# MB1-MCU-r1_0.net
KiCad netlist of a schematic drawn in Altium Designer
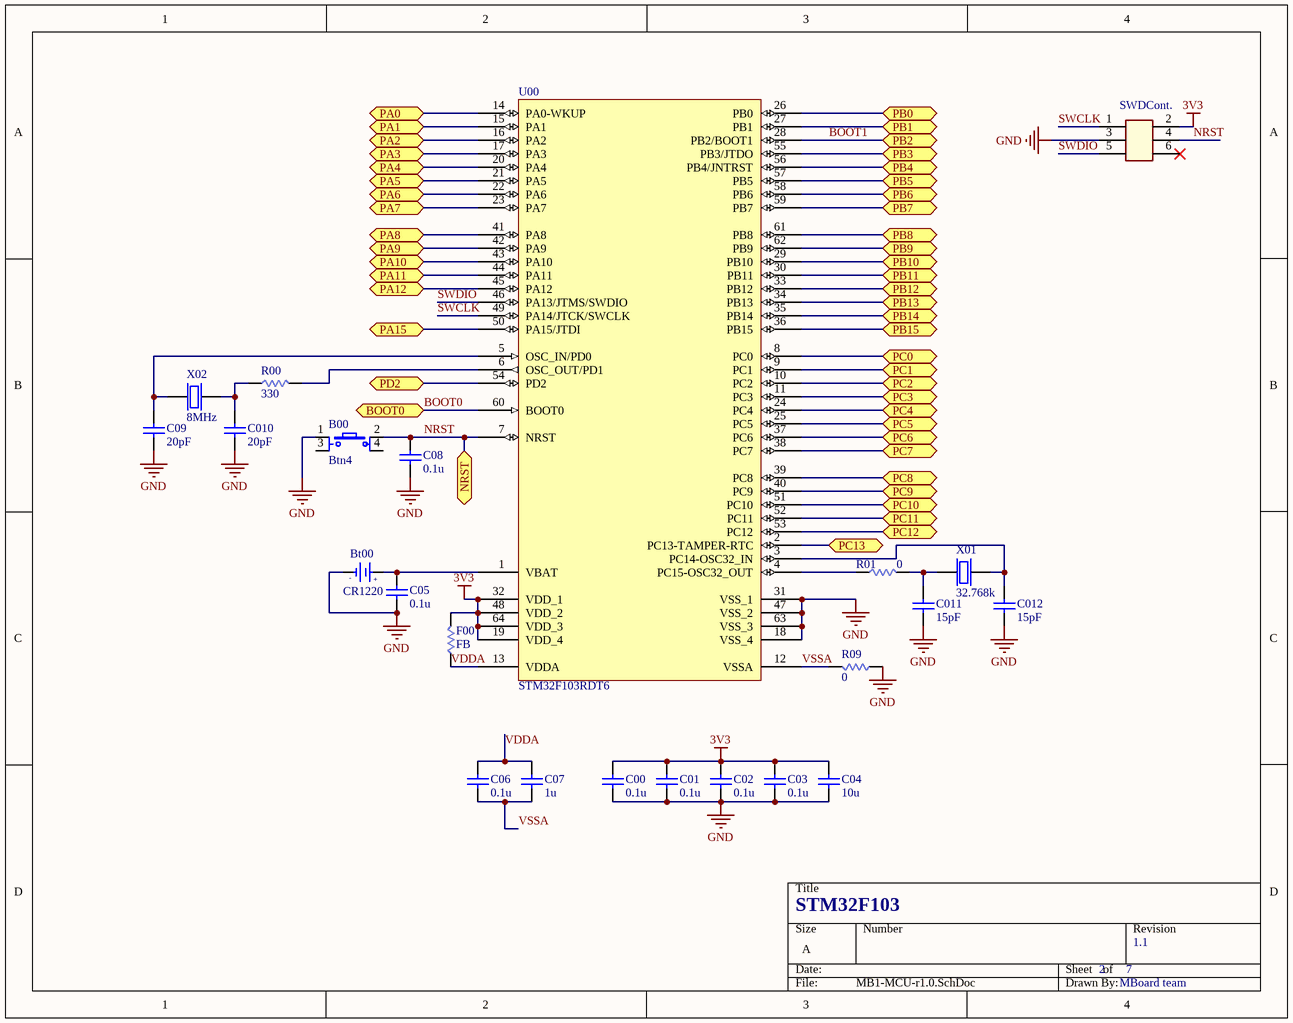
[diagram p0: MB1-MCU-r1.0.SchDoc]

(export (version "E")
  (design (tool "Eeschema 10.0.6"))
  (components
    (comp (ref "B00")
      (value "Btn4")
      (footprint "Horizon_SW_4pin_rectangular")
      (libsource (lib "MyLib") (part "Btn4"))
    )
    (comp (ref "Bt00")
      (value "CR1220")
      (footprint "MyLib:PIN3VSOCKET-SMD")
      (description "Battery 3VDC")
      (fields (field (name "Comment") "PIN 3V"))
      (libsource (lib "VioletofSun") (part "PIN 3V"))
    )
    (comp (ref "C00")
      (value "0.1u")
      (footprint "SM_0805_LD")
      (description "Non-polarity ceramic capacitor")
      (fields (field (name "Comment") "CAP Ceramic") (field (name "PUBLISHER") "Altium Limited"))
      (libsource (lib "HLib_schematic_lib") (part "CAP Ceramic"))
    )
    (comp (ref "C01")
      (value "0.1u")
      (footprint "SM_0805_LD")
      (description "Non-polarity ceramic capacitor")
      (fields (field (name "Comment") "CAP Ceramic") (field (name "PUBLISHER") "Altium Limited"))
      (libsource (lib "HLib_schematic_lib") (part "CAP Ceramic"))
    )
    (comp (ref "C02")
      (value "0.1u")
      (footprint "SM_0805_LD")
      (description "Non-polarity ceramic capacitor")
      (fields (field (name "Comment") "CAP Ceramic") (field (name "PUBLISHER") "Altium Limited"))
      (libsource (lib "HLib_schematic_lib") (part "CAP Ceramic"))
    )
    (comp (ref "C03")
      (value "0.1u")
      (footprint "SM_0805_LD")
      (description "Non-polarity ceramic capacitor")
      (fields (field (name "Comment") "CAP Ceramic") (field (name "PUBLISHER") "Altium Limited"))
      (libsource (lib "HLib_schematic_lib") (part "CAP Ceramic"))
    )
    (comp (ref "C04")
      (value "10u")
      (footprint "SM_0805_LD")
      (description "Non-polarity ceramic capacitor")
      (fields (field (name "Comment") "CAP Ceramic") (field (name "PUBLISHER") "Altium Limited"))
      (libsource (lib "HLib_schematic_lib") (part "CAP Ceramic"))
    )
    (comp (ref "C05")
      (value "0.1u")
      (footprint "SM_0805_LD")
      (description "Non-polarity ceramic capacitor")
      (fields (field (name "Comment") "CAP Ceramic") (field (name "PUBLISHER") "Altium Limited"))
      (libsource (lib "HLib_schematic_lib") (part "CAP Ceramic"))
    )
    (comp (ref "C06")
      (value "0.1u")
      (footprint "SM_0805_LD")
      (description "Non-polarity ceramic capacitor")
      (fields (field (name "Comment") "CAP Ceramic") (field (name "PUBLISHER") "Altium Limited"))
      (libsource (lib "HLib_schematic_lib") (part "CAP Ceramic"))
    )
    (comp (ref "C07")
      (value "1u")
      (footprint "SM_0805_LD")
      (description "Non-polarity ceramic capacitor")
      (fields (field (name "Comment") "CAP Ceramic") (field (name "PUBLISHER") "Altium Limited"))
      (libsource (lib "HLib_schematic_lib") (part "CAP Ceramic"))
    )
    (comp (ref "C08")
      (value "0.1u")
      (footprint "SM_0805_LD")
      (description "Non-polarity ceramic capacitor")
      (fields (field (name "Comment") "CAP Ceramic") (field (name "PUBLISHER") "Altium Limited"))
      (libsource (lib "HLib_schematic_lib") (part "CAP Ceramic"))
    )
    (comp (ref "C09")
      (value "20pF")
      (footprint "SM_0805_LD")
      (description "Non-polarity ceramic capacitor")
      (fields (field (name "Comment") "CAP Ceramic") (field (name "PUBLISHER") "Altium Limited"))
      (libsource (lib "HLib_schematic_lib") (part "CAP Ceramic"))
    )
    (comp (ref "C010")
      (value "20pF")
      (footprint "SM_0805_LD")
      (description "Non-polarity ceramic capacitor")
      (fields (field (name "Comment") "CAP Ceramic") (field (name "PUBLISHER") "Altium Limited"))
      (libsource (lib "HLib_schematic_lib") (part "CAP Ceramic"))
    )
    (comp (ref "C011")
      (value "15pF")
      (footprint "SM_0805_LD")
      (description "Non-polarity ceramic capacitor")
      (fields (field (name "Comment") "CAP Ceramic") (field (name "PUBLISHER") "Altium Limited"))
      (libsource (lib "HLib_schematic_lib") (part "CAP Ceramic"))
    )
    (comp (ref "C012")
      (value "15pF")
      (footprint "SM_0805_LD")
      (description "Non-polarity ceramic capacitor")
      (fields (field (name "Comment") "CAP Ceramic") (field (name "PUBLISHER") "Altium Limited"))
      (libsource (lib "HLib_schematic_lib") (part "CAP Ceramic"))
    )
    (comp (ref "F00")
      (value "FB")
      (footprint "SM_0805_LD")
      (description "Resistor")
      (fields (field (name "Comment") "Ferrite bead") (field (name "PUBLISHER") "Altium Limited"))
      (libsource (lib "HLib_schematic_lib") (part "R"))
    )
    (comp (ref "R00")
      (value "330")
      (footprint "SM_0805_LD")
      (description "Resistor")
      (fields (field (name "PUBLISHER") "Altium Limited"))
      (libsource (lib "HLib_schematic_lib") (part "R"))
    )
    (comp (ref "R01")
      (value "0")
      (footprint "SM_0805_LD")
      (description "Resistor")
      (fields (field (name "PUBLISHER") "Altium Limited"))
      (libsource (lib "HLib_schematic_lib") (part "R"))
    )
    (comp (ref "R09")
      (value "0")
      (footprint "SM_0805_LD")
      (description "Resistor")
      (fields (field (name "PUBLISHER") "Altium Limited"))
      (libsource (lib "HLib_schematic_lib") (part "R"))
    )
    (comp (ref "SWDCont.")
      (value "SWD")
      (footprint "Hed3x2-RA")
      (description "Header, 3-pins/row, double row,")
      (libsource (lib "HLib_connector_sch") (part "HD_3x2"))
    )
    (comp (ref "U00")
      (value "STM32F103RDT6")
      (footprint "LQFP64_L")
      (description "STM32 ARM-based 32-bit MCU with 128 Kbytes Flash, 64-pin LQFP, Industrial Temperature")
      (fields (field (name "PUBLISHER") "Altium Limited"))
      (libsource (lib "ST Microcontroller 32-Bit STM32") (part "STM32F103RBT6"))
    )
    (comp (ref "X01")
      (value "32.768k")
      (footprint "XT32-LOB")
      (fields (field (name "Comment") "Crystal 32.768 k"))
      (libsource (lib "MyLib") (part "XT32k"))
    )
    (comp (ref "X02")
      (value "8MHz")
      (footprint "HC49/US-SMD")
      (fields (field (name "Comment") "Crystal 2 pin."))
      (libsource (lib "MyLib") (part "XT2"))
    )
  )
  (nets
    (net (code "1") (name "/BOOT0") (class "Default")
      (node (ref "U00") (pin "60") (pinfunction "BOOT0_60") (pintype "input"))
    )
    (net (code "2") (name "/BOOT1") (class "Default")
      (node (ref "U00") (pin "28") (pinfunction "PB2/BOOT1_28") (pintype "bidirectional"))
    )
    (net (code "3") (name "/NRST") (class "Default")
      (node (ref "B00") (pin "2") (pinfunction "Tab_2") (pintype "passive"))
      (node (ref "C08") (pin "2") (pinfunction "2_2") (pintype "passive"))
      (node (ref "SWDCont.") (pin "4") (pinfunction "4_4") (pintype "passive"))
      (node (ref "U00") (pin "7") (pinfunction "NRST_7") (pintype "bidirectional"))
    )
    (net (code "4") (name "/PA0") (class "Default")
      (node (ref "U00") (pin "14") (pinfunction "PA0-WKUP_14") (pintype "bidirectional"))
    )
    (net (code "5") (name "/PA1") (class "Default")
      (node (ref "U00") (pin "15") (pinfunction "PA1_15") (pintype "bidirectional"))
    )
    (net (code "6") (name "/PA2") (class "Default")
      (node (ref "U00") (pin "16") (pinfunction "PA2_16") (pintype "bidirectional"))
    )
    (net (code "7") (name "/PA3") (class "Default")
      (node (ref "U00") (pin "17") (pinfunction "PA3_17") (pintype "bidirectional"))
    )
    (net (code "8") (name "/PA4") (class "Default")
      (node (ref "U00") (pin "20") (pinfunction "PA4_20") (pintype "bidirectional"))
    )
    (net (code "9") (name "/PA5") (class "Default")
      (node (ref "U00") (pin "21") (pinfunction "PA5_21") (pintype "bidirectional"))
    )
    (net (code "10") (name "/PA6") (class "Default")
      (node (ref "U00") (pin "22") (pinfunction "PA6_22") (pintype "bidirectional"))
    )
    (net (code "11") (name "/PA7") (class "Default")
      (node (ref "U00") (pin "23") (pinfunction "PA7_23") (pintype "bidirectional"))
    )
    (net (code "12") (name "/PA8") (class "Default")
      (node (ref "U00") (pin "41") (pinfunction "PA8_41") (pintype "bidirectional"))
    )
    (net (code "13") (name "/PA9") (class "Default")
      (node (ref "U00") (pin "42") (pinfunction "PA9_42") (pintype "bidirectional"))
    )
    (net (code "14") (name "/PA10") (class "Default")
      (node (ref "U00") (pin "43") (pinfunction "PA10_43") (pintype "bidirectional"))
    )
    (net (code "15") (name "/PA11") (class "Default")
      (node (ref "U00") (pin "44") (pinfunction "PA11_44") (pintype "bidirectional"))
    )
    (net (code "16") (name "/PA12") (class "Default")
      (node (ref "U00") (pin "45") (pinfunction "PA12_45") (pintype "bidirectional"))
    )
    (net (code "17") (name "/PA15") (class "Default")
      (node (ref "U00") (pin "50") (pinfunction "PA15/JTDI_50") (pintype "bidirectional"))
    )
    (net (code "18") (name "/PB0") (class "Default")
      (node (ref "U00") (pin "26") (pinfunction "PB0_26") (pintype "bidirectional"))
    )
    (net (code "19") (name "/PB1") (class "Default")
      (node (ref "U00") (pin "27") (pinfunction "PB1_27") (pintype "bidirectional"))
    )
    (net (code "20") (name "/PB3") (class "Default")
      (node (ref "U00") (pin "55") (pinfunction "PB3/JTDO_55") (pintype "bidirectional"))
    )
    (net (code "21") (name "/PB4") (class "Default")
      (node (ref "U00") (pin "56") (pinfunction "PB4/JNTRST_56") (pintype "bidirectional"))
    )
    (net (code "22") (name "/PB5") (class "Default")
      (node (ref "U00") (pin "57") (pinfunction "PB5_57") (pintype "bidirectional"))
    )
    (net (code "23") (name "/PB6") (class "Default")
      (node (ref "U00") (pin "58") (pinfunction "PB6_58") (pintype "bidirectional"))
    )
    (net (code "24") (name "/PB7") (class "Default")
      (node (ref "U00") (pin "59") (pinfunction "PB7_59") (pintype "bidirectional"))
    )
    (net (code "25") (name "/PB8") (class "Default")
      (node (ref "U00") (pin "61") (pinfunction "PB8_61") (pintype "bidirectional"))
    )
    (net (code "26") (name "/PB9") (class "Default")
      (node (ref "U00") (pin "62") (pinfunction "PB9_62") (pintype "bidirectional"))
    )
    (net (code "27") (name "/PB10") (class "Default")
      (node (ref "U00") (pin "29") (pinfunction "PB10_29") (pintype "bidirectional"))
    )
    (net (code "28") (name "/PB11") (class "Default")
      (node (ref "U00") (pin "30") (pinfunction "PB11_30") (pintype "bidirectional"))
    )
    (net (code "29") (name "/PB12") (class "Default")
      (node (ref "U00") (pin "33") (pinfunction "PB12_33") (pintype "bidirectional"))
    )
    (net (code "30") (name "/PB13") (class "Default")
      (node (ref "U00") (pin "34") (pinfunction "PB13_34") (pintype "bidirectional"))
    )
    (net (code "31") (name "/PB14") (class "Default")
      (node (ref "U00") (pin "35") (pinfunction "PB14_35") (pintype "bidirectional"))
    )
    (net (code "32") (name "/PB15") (class "Default")
      (node (ref "U00") (pin "36") (pinfunction "PB15_36") (pintype "bidirectional"))
    )
    (net (code "33") (name "/PC0") (class "Default")
      (node (ref "U00") (pin "8") (pinfunction "PC0_8") (pintype "bidirectional"))
    )
    (net (code "34") (name "/PC1") (class "Default")
      (node (ref "U00") (pin "9") (pinfunction "PC1_9") (pintype "bidirectional"))
    )
    (net (code "35") (name "/PC2") (class "Default")
      (node (ref "U00") (pin "10") (pinfunction "PC2_10") (pintype "bidirectional"))
    )
    (net (code "36") (name "/PC3") (class "Default")
      (node (ref "U00") (pin "11") (pinfunction "PC3_11") (pintype "bidirectional"))
    )
    (net (code "37") (name "/PC4") (class "Default")
      (node (ref "U00") (pin "24") (pinfunction "PC4_24") (pintype "bidirectional"))
    )
    (net (code "38") (name "/PC5") (class "Default")
      (node (ref "U00") (pin "25") (pinfunction "PC5_25") (pintype "bidirectional"))
    )
    (net (code "39") (name "/PC6") (class "Default")
      (node (ref "U00") (pin "37") (pinfunction "PC6_37") (pintype "bidirectional"))
    )
    (net (code "40") (name "/PC7") (class "Default")
      (node (ref "U00") (pin "38") (pinfunction "PC7_38") (pintype "bidirectional"))
    )
    (net (code "41") (name "/PC8") (class "Default")
      (node (ref "U00") (pin "39") (pinfunction "PC8_39") (pintype "bidirectional"))
    )
    (net (code "42") (name "/PC9") (class "Default")
      (node (ref "U00") (pin "40") (pinfunction "PC9_40") (pintype "bidirectional"))
    )
    (net (code "43") (name "/PC10") (class "Default")
      (node (ref "U00") (pin "51") (pinfunction "PC10_51") (pintype "bidirectional"))
    )
    (net (code "44") (name "/PC11") (class "Default")
      (node (ref "U00") (pin "52") (pinfunction "PC11_52") (pintype "bidirectional"))
    )
    (net (code "45") (name "/PC12") (class "Default")
      (node (ref "U00") (pin "53") (pinfunction "PC12_53") (pintype "bidirectional"))
    )
    (net (code "46") (name "/PC13") (class "Default")
      (node (ref "U00") (pin "2") (pinfunction "PC13-TAMPER-RTC_2") (pintype "bidirectional"))
    )
    (net (code "47") (name "/PD2") (class "Default")
      (node (ref "U00") (pin "54") (pinfunction "PD2_54") (pintype "bidirectional"))
    )
    (net (code "48") (name "/SWCLK") (class "Default")
      (node (ref "SWDCont.") (pin "1") (pinfunction "1_1") (pintype "passive"))
      (node (ref "U00") (pin "49") (pinfunction "PA14/JTCK/SWCLK_49") (pintype "bidirectional"))
    )
    (net (code "49") (name "/SWDIO") (class "Default")
      (node (ref "SWDCont.") (pin "5") (pinfunction "5_5") (pintype "passive"))
      (node (ref "U00") (pin "46") (pinfunction "PA13/JTMS/SWDIO_46") (pintype "bidirectional"))
    )
    (net (code "50") (name "/VDDA") (class "Default")
      (node (ref "C06") (pin "2") (pinfunction "2_2") (pintype "passive"))
      (node (ref "C07") (pin "2") (pinfunction "2_2") (pintype "passive"))
      (node (ref "F00") (pin "1") (pinfunction "1_1") (pintype "passive"))
      (node (ref "U00") (pin "13") (pinfunction "VDDA_13") (pintype "power_in"))
    )
    (net (code "51") (name "/VSSA") (class "Default")
      (node (ref "C06") (pin "1") (pinfunction "1_1") (pintype "passive"))
      (node (ref "C07") (pin "1") (pinfunction "1_1") (pintype "passive"))
      (node (ref "R09") (pin "2") (pinfunction "2_2") (pintype "passive"))
      (node (ref "U00") (pin "12") (pinfunction "VSSA_12") (pintype "power_in"))
    )
    (net (code "52") (name "3V3") (class "Default")
      (node (ref "C00") (pin "2") (pinfunction "2_2") (pintype "passive"))
      (node (ref "C01") (pin "2") (pinfunction "2_2") (pintype "passive"))
      (node (ref "C02") (pin "2") (pinfunction "2_2") (pintype "passive"))
      (node (ref "C03") (pin "2") (pinfunction "2_2") (pintype "passive"))
      (node (ref "C04") (pin "2") (pinfunction "2_2") (pintype "passive"))
      (node (ref "F00") (pin "2") (pinfunction "2_2") (pintype "passive"))
      (node (ref "SWDCont.") (pin "2") (pinfunction "2_2") (pintype "passive"))
      (node (ref "U00") (pin "19") (pinfunction "VDD_4_19") (pintype "power_in"))
      (node (ref "U00") (pin "32") (pinfunction "VDD_1_32") (pintype "power_in"))
      (node (ref "U00") (pin "48") (pinfunction "VDD_2_48") (pintype "power_in"))
      (node (ref "U00") (pin "64") (pinfunction "VDD_3_64") (pintype "power_in"))
    )
    (net (code "53") (name "GND") (class "Default")
      (node (ref "B00") (pin "1") (pinfunction "Tab_1") (pintype "passive"))
      (node (ref "Bt00") (pin "2") (pinfunction "GND_2") (pintype "passive"))
      (node (ref "C00") (pin "1") (pinfunction "1_1") (pintype "passive"))
      (node (ref "C01") (pin "1") (pinfunction "1_1") (pintype "passive"))
      (node (ref "C010") (pin "1") (pinfunction "1_1") (pintype "passive"))
      (node (ref "C011") (pin "1") (pinfunction "1_1") (pintype "passive"))
      (node (ref "C012") (pin "1") (pinfunction "1_1") (pintype "passive"))
      (node (ref "C02") (pin "1") (pinfunction "1_1") (pintype "passive"))
      (node (ref "C03") (pin "1") (pinfunction "1_1") (pintype "passive"))
      (node (ref "C04") (pin "1") (pinfunction "1_1") (pintype "passive"))
      (node (ref "C05") (pin "1") (pinfunction "1_1") (pintype "passive"))
      (node (ref "C08") (pin "1") (pinfunction "1_1") (pintype "passive"))
      (node (ref "C09") (pin "1") (pinfunction "1_1") (pintype "passive"))
      (node (ref "R09") (pin "1") (pinfunction "1_1") (pintype "passive"))
      (node (ref "SWDCont.") (pin "3") (pinfunction "3_3") (pintype "passive"))
      (node (ref "U00") (pin "18") (pinfunction "VSS_4_18") (pintype "power_in"))
      (node (ref "U00") (pin "31") (pinfunction "VSS_1_31") (pintype "power_in"))
      (node (ref "U00") (pin "47") (pinfunction "VSS_2_47") (pintype "power_in"))
      (node (ref "U00") (pin "63") (pinfunction "VSS_3_63") (pintype "power_in"))
    )
    (net (code "54") (name "Net-(Bt00-+3V)") (class "Default")
      (node (ref "Bt00") (pin "1") (pinfunction "+3V_1") (pintype "passive"))
      (node (ref "C05") (pin "2") (pinfunction "2_2") (pintype "passive"))
      (node (ref "U00") (pin "1") (pinfunction "VBAT_1") (pintype "power_in"))
    )
    (net (code "55") (name "Net-(U00-OSC_IN{slash}PD0)") (class "Default")
      (node (ref "C09") (pin "2") (pinfunction "2_2") (pintype "passive"))
      (node (ref "U00") (pin "5") (pinfunction "OSC_IN/PD0_5") (pintype "input"))
      (node (ref "X02") (pin "1") (pinfunction "Xin_1") (pintype "passive"))
    )
    (net (code "56") (name "Net-(U00-OSC_OUT{slash}PD1)") (class "Default")
      (node (ref "R00") (pin "2") (pinfunction "2_2") (pintype "passive"))
      (node (ref "U00") (pin "6") (pinfunction "OSC_OUT/PD1_6") (pintype "output"))
    )
    (net (code "57") (name "Net-(U00-PC14-OSC32_IN)") (class "Default")
      (node (ref "C012") (pin "2") (pinfunction "2_2") (pintype "passive"))
      (node (ref "U00") (pin "3") (pinfunction "PC14-OSC32_IN_3") (pintype "bidirectional"))
      (node (ref "X01") (pin "2") (pinfunction "Xout_2") (pintype "passive"))
    )
    (net (code "58") (name "Net-(U00-PC15-OSC32_OUT)") (class "Default")
      (node (ref "R01") (pin "1") (pinfunction "1_1") (pintype "passive"))
      (node (ref "U00") (pin "4") (pinfunction "PC15-OSC32_OUT_4") (pintype "bidirectional"))
    )
    (net (code "59") (name "Net-(X01-Xin)") (class "Default")
      (node (ref "C011") (pin "2") (pinfunction "2_2") (pintype "passive"))
      (node (ref "R01") (pin "2") (pinfunction "2_2") (pintype "passive"))
      (node (ref "X01") (pin "1") (pinfunction "Xin_1") (pintype "passive"))
    )
    (net (code "60") (name "Net-(X02-Xout)") (class "Default")
      (node (ref "C010") (pin "2") (pinfunction "2_2") (pintype "passive"))
      (node (ref "R00") (pin "1") (pinfunction "1_1") (pintype "passive"))
      (node (ref "X02") (pin "2") (pinfunction "Xout_2") (pintype "passive"))
    )
    (net (code "61") (name "unconnected-(B00-Tab-Pad3)") (class "Default")
      (node (ref "B00") (pin "3") (pinfunction "Tab_3") (pintype "passive"))
    )
    (net (code "62") (name "unconnected-(B00-Tab-Pad4)") (class "Default")
      (node (ref "B00") (pin "4") (pinfunction "Tab_4") (pintype "passive"))
    )
    (net (code "63") (name "unconnected-(SWDCont.-Pad6)") (class "Default")
      (node (ref "SWDCont.") (pin "6") (pinfunction "6_6") (pintype "passive+no_connect"))
    )
  )
)
